# BW1097_MIPI_IO.net
KiCad netlist of a schematic drawn in Altium Designer
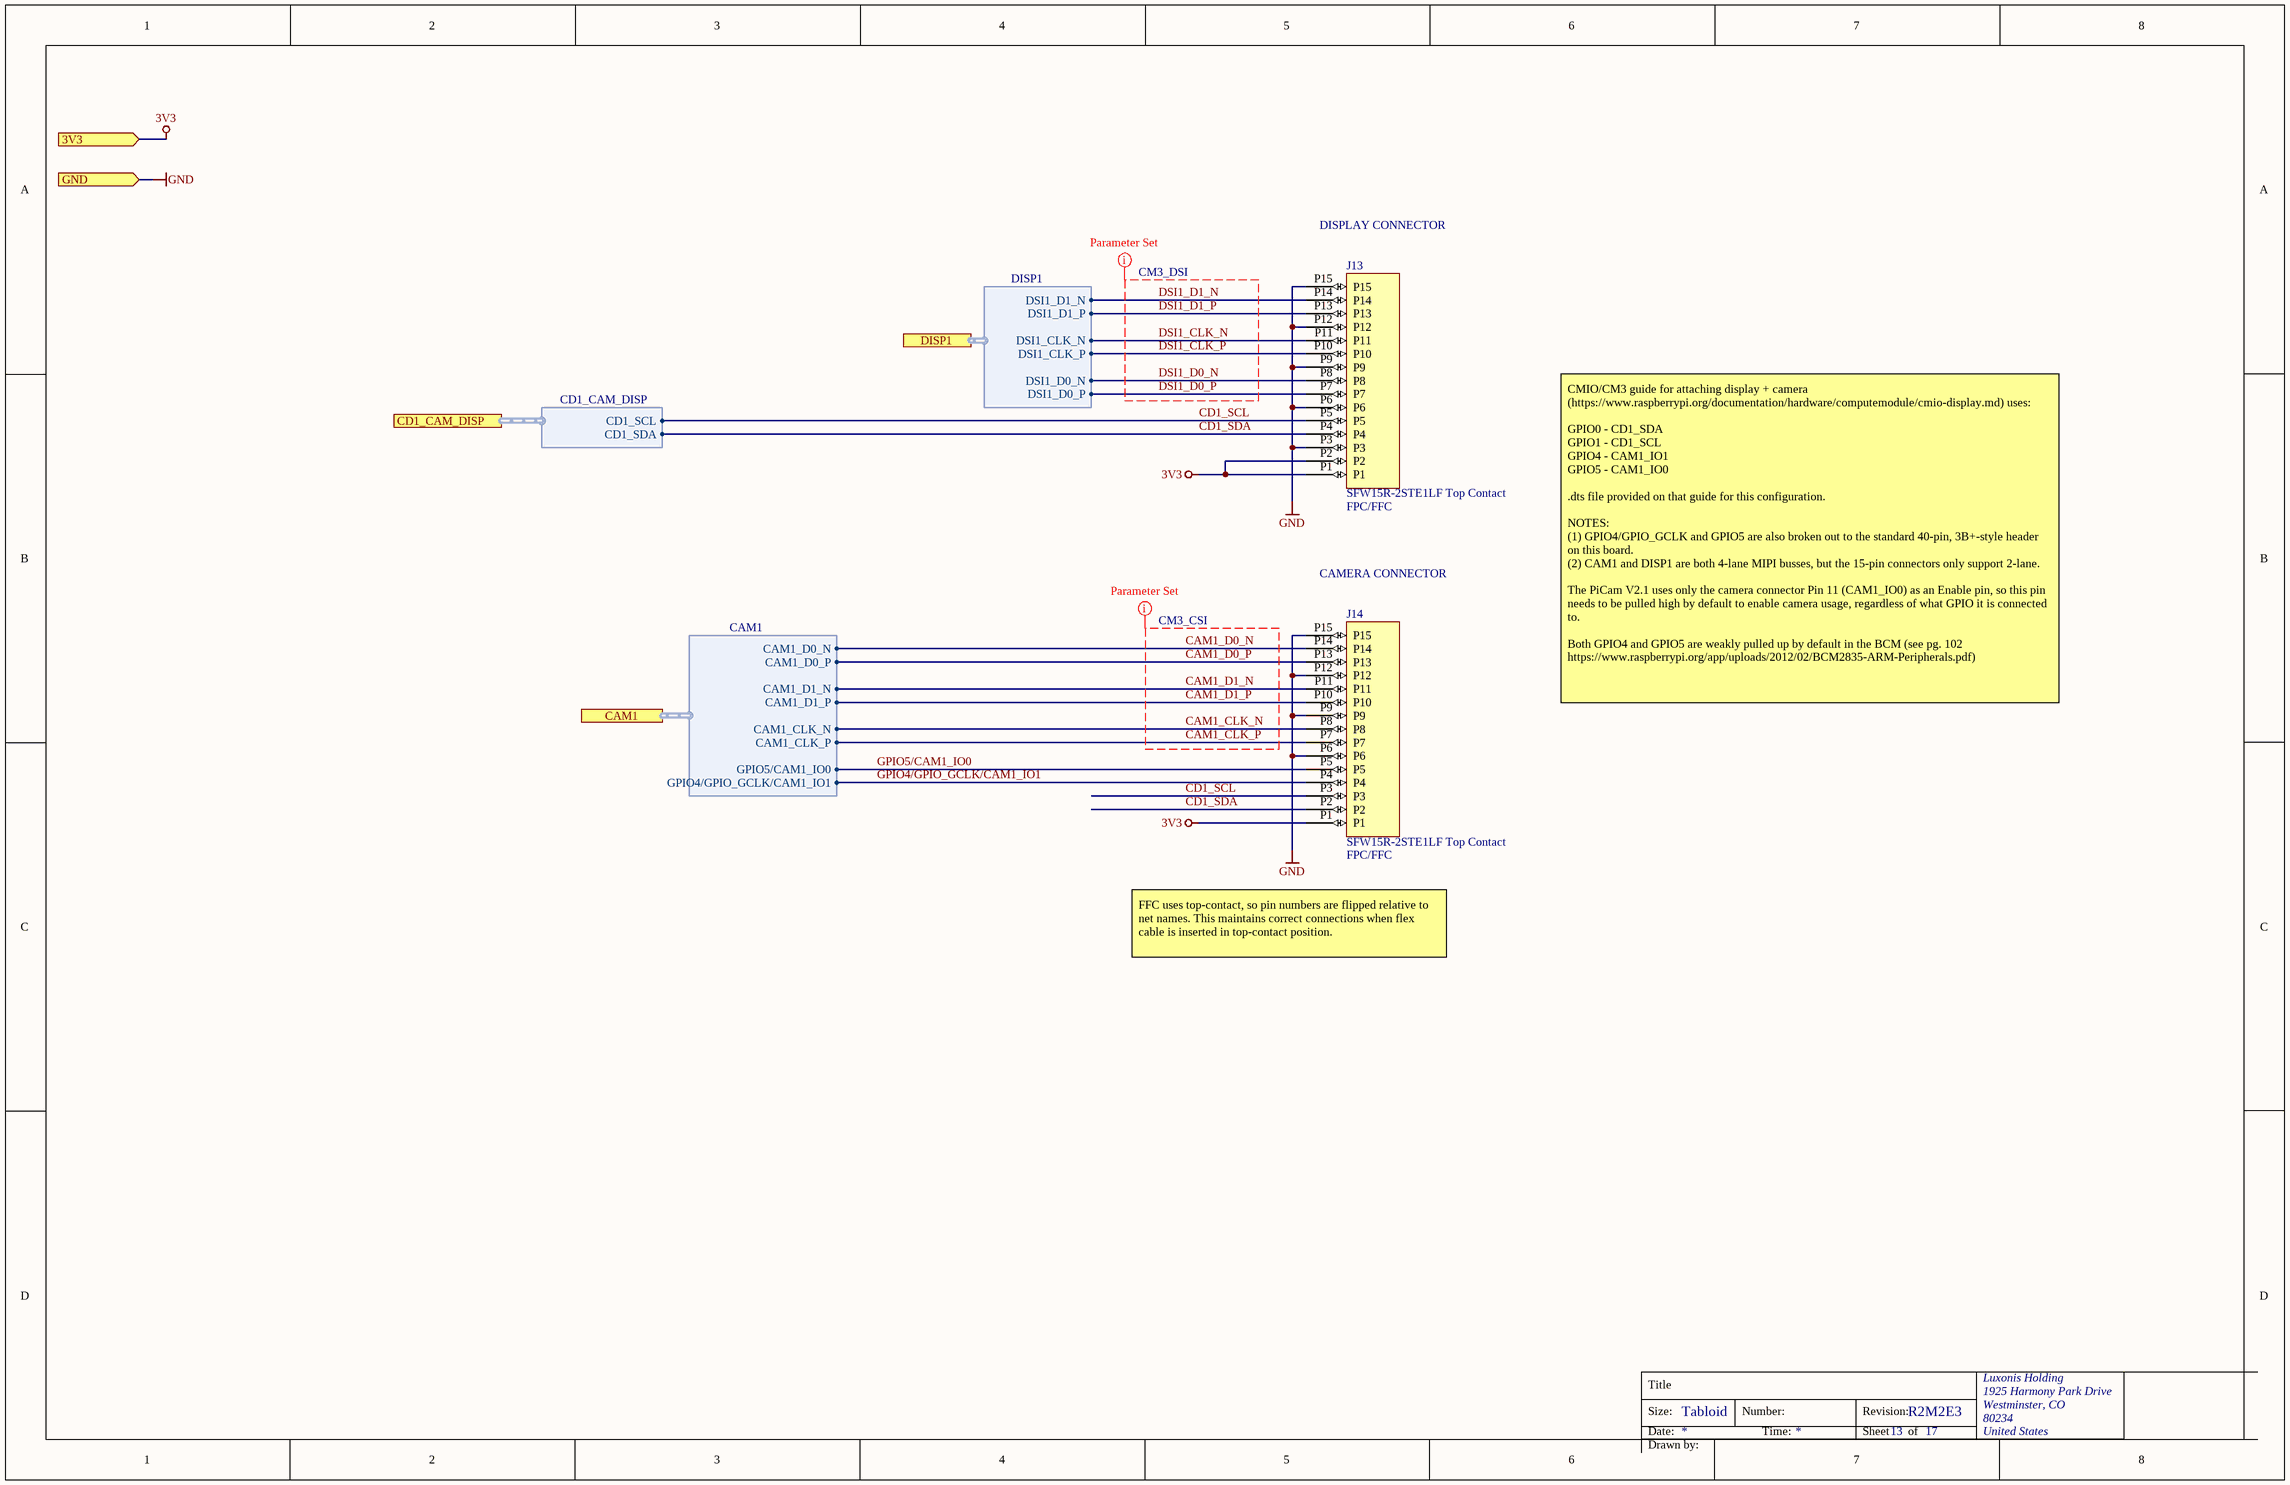
[diagram p0: BW1097_MIPI_IO.SchDoc]

(export (version "E")
  (design (tool "Eeschema 10.0.6"))
  (components
    (comp (ref "J13")
      (value "SFW15R-2STE1LF Top Contact")
      (footprint "LuxonisMaster:SFW15R-2STE1LF")
      (description "CONN FFC FPC TOP 15POS 1MM R/A")
      (fields (field (name "MANUFACTURER") "Amphenol") (field (name "COMPONENT SUBTYPE") "FPC/FFC"))
      (libsource (lib "LuxonisMaster") (part "SFW15R-2STE1LF"))
    )
    (comp (ref "J14")
      (value "SFW15R-2STE1LF Top Contact")
      (footprint "LuxonisMaster:SFW15R-2STE1LF")
      (description "CONN FFC FPC TOP 15POS 1MM R/A")
      (fields (field (name "MANUFACTURER") "Amphenol") (field (name "COMPONENT SUBTYPE") "FPC/FFC"))
      (libsource (lib "LuxonisMaster") (part "SFW15R-2STE1LF"))
    )
  )
  (nets
    (net (code "4") (name "/CAM1_CLK_N") (class "Default")
      (node (ref "J14") (pin "P8") (pinfunction "P8_P8") (pintype "bidirectional"))
    )
    (net (code "5") (name "/CAM1_CLK_P") (class "Default")
      (node (ref "J14") (pin "P7") (pinfunction "P7_P7") (pintype "bidirectional"))
    )
    (net (code "6") (name "/CAM1_D0_N") (class "Default")
      (node (ref "J14") (pin "P14") (pinfunction "P14_P14") (pintype "bidirectional"))
    )
    (net (code "7") (name "/CAM1_D0_P") (class "Default")
      (node (ref "J14") (pin "P13") (pinfunction "P13_P13") (pintype "bidirectional"))
    )
    (net (code "8") (name "/CAM1_D1_N") (class "Default")
      (node (ref "J14") (pin "P11") (pinfunction "P11_P11") (pintype "bidirectional"))
    )
    (net (code "9") (name "/CAM1_D1_P") (class "Default")
      (node (ref "J14") (pin "P10") (pinfunction "P10_P10") (pintype "bidirectional"))
    )
    (net (code "10") (name "/CD1_SCL") (class "Default")
      (node (ref "J13") (pin "P5") (pinfunction "P5_P5") (pintype "bidirectional"))
      (node (ref "J14") (pin "P3") (pinfunction "P3_P3") (pintype "bidirectional"))
    )
    (net (code "11") (name "/CD1_SDA") (class "Default")
      (node (ref "J13") (pin "P4") (pinfunction "P4_P4") (pintype "bidirectional"))
      (node (ref "J14") (pin "P2") (pinfunction "P2_P2") (pintype "bidirectional"))
    )
    (net (code "12") (name "/DSI1_CLK_N") (class "Default")
      (node (ref "J13") (pin "P11") (pinfunction "P11_P11") (pintype "bidirectional"))
    )
    (net (code "13") (name "/DSI1_CLK_P") (class "Default")
      (node (ref "J13") (pin "P10") (pinfunction "P10_P10") (pintype "bidirectional"))
    )
    (net (code "14") (name "/DSI1_D0_N") (class "Default")
      (node (ref "J13") (pin "P8") (pinfunction "P8_P8") (pintype "bidirectional"))
    )
    (net (code "15") (name "/DSI1_D0_P") (class "Default")
      (node (ref "J13") (pin "P7") (pinfunction "P7_P7") (pintype "bidirectional"))
    )
    (net (code "16") (name "/DSI1_D1_N") (class "Default")
      (node (ref "J13") (pin "P14") (pinfunction "P14_P14") (pintype "bidirectional"))
    )
    (net (code "17") (name "/DSI1_D1_P") (class "Default")
      (node (ref "J13") (pin "P13") (pinfunction "P13_P13") (pintype "bidirectional"))
    )
    (net (code "18") (name "/GPIO4{slash}GPIO_GCLK{slash}CAM1_IO1") (class "Default")
      (node (ref "J14") (pin "P4") (pinfunction "P4_P4") (pintype "bidirectional"))
    )
    (net (code "19") (name "/GPIO5{slash}CAM1_IO0") (class "Default")
      (node (ref "J14") (pin "P5") (pinfunction "P5_P5") (pintype "bidirectional"))
    )
    (net (code "23") (name "3V3") (class "Default")
      (node (ref "J13") (pin "P1") (pinfunction "P1_P1") (pintype "bidirectional"))
      (node (ref "J13") (pin "P2") (pinfunction "P2_P2") (pintype "bidirectional"))
      (node (ref "J14") (pin "P1") (pinfunction "P1_P1") (pintype "bidirectional"))
    )
    (net (code "24") (name "GND") (class "Default")
      (node (ref "J13") (pin "P12") (pinfunction "P12_P12") (pintype "bidirectional"))
      (node (ref "J13") (pin "P15") (pinfunction "P15_P15") (pintype "bidirectional"))
      (node (ref "J13") (pin "P3") (pinfunction "P3_P3") (pintype "bidirectional"))
      (node (ref "J13") (pin "P6") (pinfunction "P6_P6") (pintype "bidirectional"))
      (node (ref "J13") (pin "P9") (pinfunction "P9_P9") (pintype "bidirectional"))
      (node (ref "J14") (pin "P12") (pinfunction "P12_P12") (pintype "bidirectional"))
      (node (ref "J14") (pin "P15") (pinfunction "P15_P15") (pintype "bidirectional"))
      (node (ref "J14") (pin "P6") (pinfunction "P6_P6") (pintype "bidirectional"))
      (node (ref "J14") (pin "P9") (pinfunction "P9_P9") (pintype "bidirectional"))
    )
  )
)
